# D5035-01.net
KiCad netlist of a schematic drawn in Altium Designer
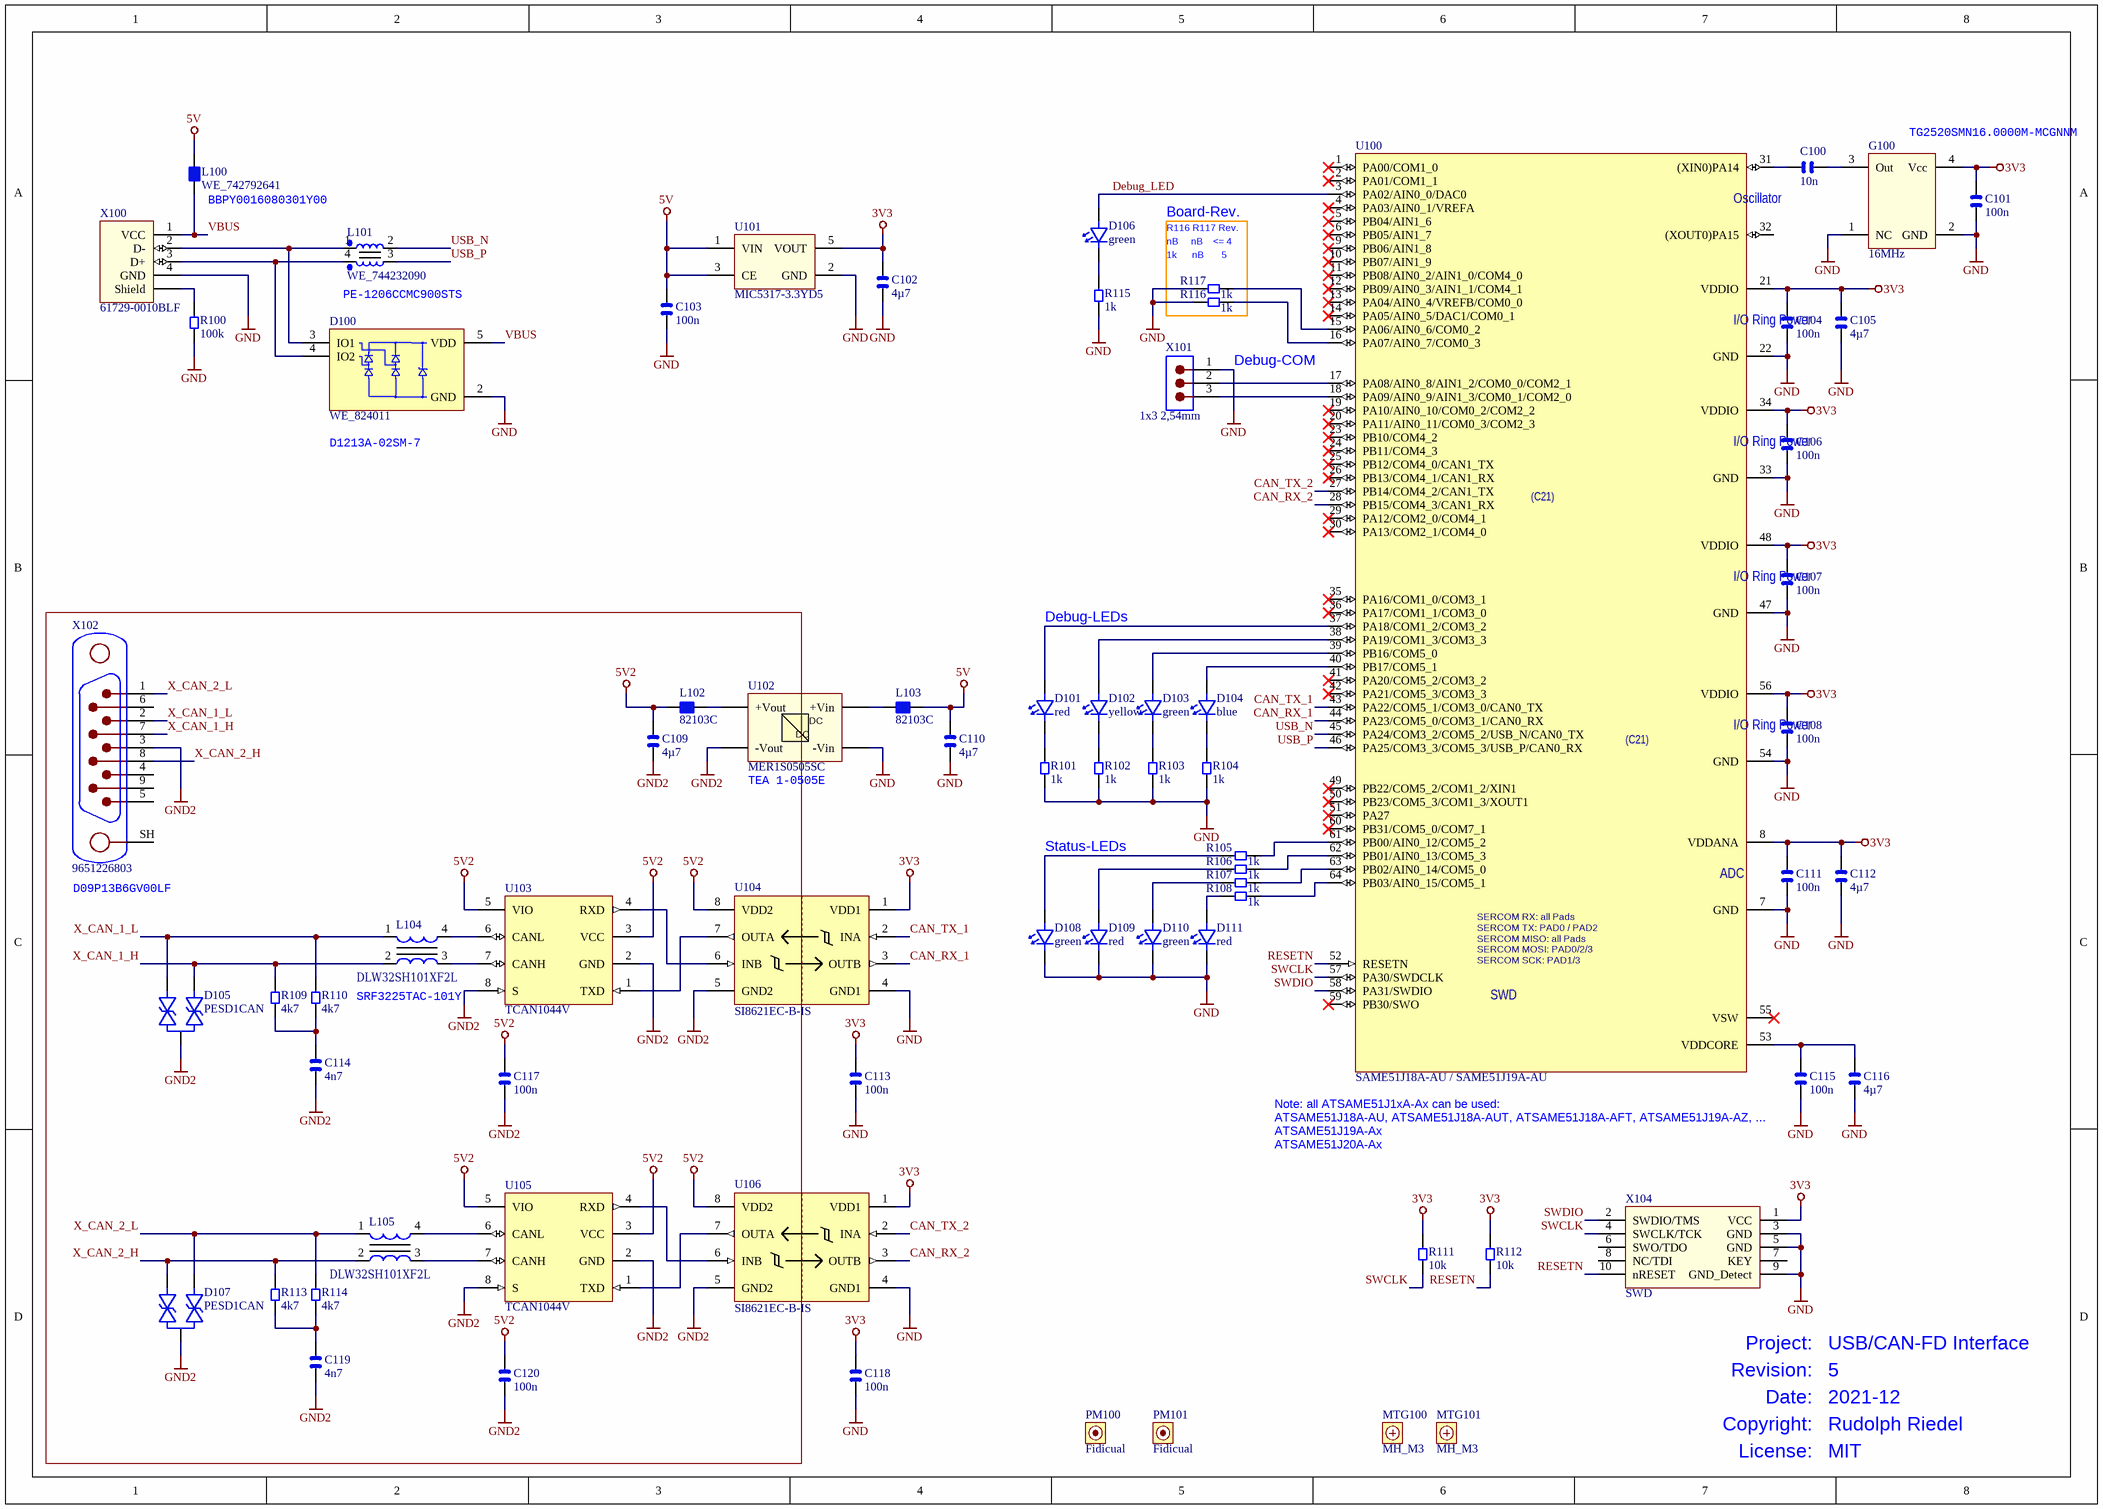
[diagram p0: D5035-01.SchDoc]

(export (version "E")
  (design (tool "Eeschema 10.0.6"))
  (components
    (comp (ref "C100")
      (value "10n")
      (footprint "CAPC1608X09L")
      (description "0603 Chip Capacitor")
      (fields (field (name "PART NUMBER") "CAPC_0603") (field (name "EDITOR") "rriedel"))
      (libsource (lib "HW-Labor_GF") (part "CAP_2_V2"))
    )
    (comp (ref "C101")
      (value "100n")
      (footprint "CAPC1608X09L")
      (description "0603 Chip Capacitor")
      (fields (field (name "PART NUMBER") "CAPC_0603") (field (name "EDITOR") "rriedel"))
      (libsource (lib "HW-Labor_GF") (part "CAP_2_V2"))
    )
    (comp (ref "C102")
      (value "4µ7")
      (footprint "CAPC2012X14L")
      (description "0805 Chip Capacitor")
      (fields (field (name "PART NUMBER") "CAPC_0805") (field (name "EDITOR") "rriedel"))
      (libsource (lib "HW-Labor_GF") (part "CAP_2_V2"))
    )
    (comp (ref "C103")
      (value "100n")
      (footprint "CAPC1608X09L")
      (description "0603 Chip Capacitor")
      (fields (field (name "PART NUMBER") "CAPC_0603") (field (name "EDITOR") "rriedel"))
      (libsource (lib "HW-Labor_GF") (part "CAP_2_V2"))
    )
    (comp (ref "C104")
      (value "100n")
      (footprint "CAPC1608X09L")
      (description "0603 Chip Capacitor")
      (fields (field (name "PART NUMBER") "CAPC_0603") (field (name "EDITOR") "rriedel"))
      (libsource (lib "HW-Labor_GF") (part "CAP_2_V2"))
    )
    (comp (ref "C105")
      (value "4µ7")
      (footprint "CAPC2012X14L")
      (description "0805 Chip Capacitor")
      (fields (field (name "PART NUMBER") "CAPC_0805") (field (name "EDITOR") "rriedel"))
      (libsource (lib "HW-Labor_GF") (part "CAP_2_V2"))
    )
    (comp (ref "C106")
      (value "100n")
      (footprint "CAPC1608X09L")
      (description "0603 Chip Capacitor")
      (fields (field (name "PART NUMBER") "CAPC_0603") (field (name "EDITOR") "rriedel"))
      (libsource (lib "HW-Labor_GF") (part "CAP_2_V2"))
    )
    (comp (ref "C107")
      (value "100n")
      (footprint "CAPC1608X09L")
      (description "0603 Chip Capacitor")
      (fields (field (name "PART NUMBER") "CAPC_0603") (field (name "EDITOR") "rriedel"))
      (libsource (lib "HW-Labor_GF") (part "CAP_2_V2"))
    )
    (comp (ref "C108")
      (value "100n")
      (footprint "CAPC1608X09L")
      (description "0603 Chip Capacitor")
      (fields (field (name "PART NUMBER") "CAPC_0603") (field (name "EDITOR") "rriedel"))
      (libsource (lib "HW-Labor_GF") (part "CAP_2_V2"))
    )
    (comp (ref "C109")
      (value "4µ7")
      (footprint "CAPC2012X14L")
      (description "0805 Chip Capacitor")
      (fields (field (name "PART NUMBER") "CAPC_0805") (field (name "EDITOR") "rriedel"))
      (libsource (lib "HW-Labor_GF") (part "CAP_2_V2"))
    )
    (comp (ref "C110")
      (value "4µ7")
      (footprint "CAPC2012X14L")
      (description "0805 Chip Capacitor")
      (fields (field (name "PART NUMBER") "CAPC_0805") (field (name "EDITOR") "rriedel"))
      (libsource (lib "HW-Labor_GF") (part "CAP_2_V2"))
    )
    (comp (ref "C111")
      (value "100n")
      (footprint "CAPC1608X09L")
      (description "0603 Chip Capacitor")
      (fields (field (name "PART NUMBER") "CAPC_0603") (field (name "EDITOR") "rriedel"))
      (libsource (lib "HW-Labor_GF") (part "CAP_2_V2"))
    )
    (comp (ref "C112")
      (value "4µ7")
      (footprint "CAPC2012X14L")
      (description "0805 Chip Capacitor")
      (fields (field (name "PART NUMBER") "CAPC_0805") (field (name "EDITOR") "rriedel"))
      (libsource (lib "HW-Labor_GF") (part "CAP_2_V2"))
    )
    (comp (ref "C113")
      (value "100n")
      (footprint "CAPC1608X09L")
      (description "0603 Chip Capacitor")
      (fields (field (name "PART NUMBER") "CAPC_0603") (field (name "EDITOR") "rriedel"))
      (libsource (lib "HW-Labor_GF") (part "CAP_2_V2"))
    )
    (comp (ref "C114")
      (value "4n7")
      (footprint "CAPC2012X14L")
      (description "0805 Chip Capacitor")
      (fields (field (name "PART NUMBER") "CAPC_0805") (field (name "EDITOR") "rriedel"))
      (libsource (lib "HW-Labor_GF") (part "CAP_2_V2"))
    )
    (comp (ref "C115")
      (value "100n")
      (footprint "CAPC1608X09L")
      (description "0603 Chip Capacitor")
      (fields (field (name "PART NUMBER") "CAPC_0603") (field (name "EDITOR") "rriedel"))
      (libsource (lib "HW-Labor_GF") (part "CAP_2_V2"))
    )
    (comp (ref "C116")
      (value "4µ7")
      (footprint "CAPC2012X14L")
      (description "0805 Chip Capacitor")
      (fields (field (name "PART NUMBER") "CAPC_0805") (field (name "EDITOR") "rriedel"))
      (libsource (lib "HW-Labor_GF") (part "CAP_2_V2"))
    )
    (comp (ref "C117")
      (value "100n")
      (footprint "CAPC1608X09L")
      (description "0603 Chip Capacitor")
      (fields (field (name "PART NUMBER") "CAPC_0603") (field (name "EDITOR") "rriedel"))
      (libsource (lib "HW-Labor_GF") (part "CAP_2_V2"))
    )
    (comp (ref "C118")
      (value "100n")
      (footprint "CAPC1608X09L")
      (description "0603 Chip Capacitor")
      (fields (field (name "PART NUMBER") "CAPC_0603") (field (name "EDITOR") "rriedel"))
      (libsource (lib "HW-Labor_GF") (part "CAP_2_V2"))
    )
    (comp (ref "C119")
      (value "4n7")
      (footprint "CAPC2012X14L")
      (description "0805 Chip Capacitor")
      (fields (field (name "PART NUMBER") "CAPC_0805") (field (name "EDITOR") "rriedel"))
      (libsource (lib "HW-Labor_GF") (part "CAP_2_V2"))
    )
    (comp (ref "C120")
      (value "100n")
      (footprint "CAPC1608X09L")
      (description "0603 Chip Capacitor")
      (fields (field (name "PART NUMBER") "CAPC_0603") (field (name "EDITOR") "rriedel"))
      (libsource (lib "HW-Labor_GF") (part "CAP_2_V2"))
    )
    (comp (ref "D100")
      (value "WE_824011")
      (footprint "SOT95P280X110-5N")
      (description "TVS Diode Array WE-TVS")
      (fields
        (field (name "MANUFACTURER") "Wuerth")
        (field (name "DISTRIBUTOR_1_PART_NUMBER") "732-4465-1-ND")
        (field (name "EDITOR") "rriedel")
      )
      (libsource (lib "HW-Labor_GF") (part "WE-824011"))
    )
    (comp (ref "D101")
      (value "red")
      (footprint "DIOC1608X06N_LED")
      (description "LED, 0603")
      (fields (field (name "PART NUMBER") "LED_0603") (field (name "EDITOR") "rriedel"))
      (libsource (lib "HW-Labor_GF") (part "LED_generic"))
    )
    (comp (ref "D102")
      (value "yellow")
      (footprint "DIOC1608X06N_LED")
      (description "LED, 0603")
      (fields (field (name "PART NUMBER") "LED_0603") (field (name "EDITOR") "rriedel"))
      (libsource (lib "HW-Labor_GF") (part "LED_generic"))
    )
    (comp (ref "D103")
      (value "green")
      (footprint "DIOC1608X06N_LED")
      (description "LED, 0603")
      (fields (field (name "PART NUMBER") "LED_0603") (field (name "EDITOR") "rriedel"))
      (libsource (lib "HW-Labor_GF") (part "LED_generic"))
    )
    (comp (ref "D104")
      (value "blue")
      (footprint "DIOC1608X06N_LED")
      (description "LED, 0603")
      (fields (field (name "PART NUMBER") "LED_0603") (field (name "EDITOR") "rriedel"))
      (libsource (lib "HW-Labor_GF") (part "LED_generic"))
    )
    (comp (ref "D105")
      (value "PESD1CAN")
      (footprint "SOT95P280X110-3N")
      (description "CAN bus ESD protection diode")
      (fields
        (field (name "MANUFACTURER") "Nexperia")
        (field (name "DISTRIBUTOR_1_PART_NUMBER") "1727-3817-1-ND")
        (field (name "EDITOR") "rriedel")
      )
      (libsource (lib "HW-Labor_GF") (part "PESD1CAN"))
    )
    (comp (ref "D106")
      (value "green")
      (footprint "DIOC1608X06N_LED")
      (description "LED, 0603")
      (fields (field (name "PART NUMBER") "LED_0603") (field (name "EDITOR") "rriedel"))
      (libsource (lib "HW-Labor_GF") (part "LED_generic"))
    )
    (comp (ref "D107")
      (value "PESD1CAN")
      (footprint "SOT95P280X110-3N")
      (description "CAN bus ESD protection diode")
      (fields
        (field (name "MANUFACTURER") "Nexperia")
        (field (name "DISTRIBUTOR_1_PART_NUMBER") "1727-3817-1-ND")
        (field (name "EDITOR") "rriedel")
      )
      (libsource (lib "HW-Labor_GF") (part "PESD1CAN"))
    )
    (comp (ref "D108")
      (value "green")
      (footprint "DIOC1608X06N_LED")
      (description "LED, 0603")
      (fields (field (name "PART NUMBER") "LED_0603") (field (name "EDITOR") "rriedel"))
      (libsource (lib "HW-Labor_GF") (part "LED_generic"))
    )
    (comp (ref "D109")
      (value "red")
      (footprint "DIOC1608X06N_LED")
      (description "LED, 0603")
      (fields (field (name "PART NUMBER") "LED_0603") (field (name "EDITOR") "rriedel"))
      (libsource (lib "HW-Labor_GF") (part "LED_generic"))
    )
    (comp (ref "D110")
      (value "green")
      (footprint "DIOC1608X06N_LED")
      (description "LED, 0603")
      (fields (field (name "PART NUMBER") "LED_0603") (field (name "EDITOR") "rriedel"))
      (libsource (lib "HW-Labor_GF") (part "LED_generic"))
    )
    (comp (ref "D111")
      (value "red")
      (footprint "DIOC1608X06N_LED")
      (description "LED, 0603")
      (fields (field (name "PART NUMBER") "LED_0603") (field (name "EDITOR") "rriedel"))
      (libsource (lib "HW-Labor_GF") (part "LED_generic"))
    )
    (comp (ref "G100")
      (value "16MHz")
      (footprint "TG2520")
      (description "16MHz Oscillator, +/- 0.5ppm")
      (fields
        (field (name "PART NUMBER") "TG2520SMN16.0000M-MCGNNM")
        (field (name "MANUFACTURER") "Epson")
        (field (name "EDITOR") "rriedel")
      )
      (libsource (lib "HW-Labor_GF") (part "TG2520"))
    )
    (comp (ref "L100")
      (value "WE_742792641")
      (footprint "INDC1608X06L")
      (description "SMT EMI suppression ferrite bead WE-CBF")
      (fields
        (field (name "MANUFACTURER") "Wuerth")
        (field (name "DISTRIBUTOR_1_PART_NUMBER") "732-1592-1-ND")
        (field (name "EDITOR") "rriedel")
      )
      (libsource (lib "HW-Labor_GF") (part "IND_2_V1"))
    )
    (comp (ref "L101")
      (value "WE_744232090")
      (footprint "WE_744232090")
      (description "SMD common mode noise suppressor WE-CNSW")
      (fields
        (field (name "MANUFACTURER") "Wuerth")
        (field (name "DISTRIBUTOR_1_PART_NUMBER") "732-1469-1-ND")
        (field (name "EDITOR") "rriedel")
      )
      (libsource (lib "HW-Labor_GF") (part "WE_744232090"))
    )
    (comp (ref "L102")
      (value "82103C")
      (footprint "Murata_8200C")
      (description "10µH, 0,5A, 400mR")
      (fields
        (field (name "MANUFACTURER") "Murata")
        (field (name "DISTRIBUTOR_1_PART_NUMBER") "811-2473-1-ND")
        (field (name "EDITOR") "rriedel")
      )
      (libsource (lib "HW-Labor_GF") (part "IND_2_V1"))
    )
    (comp (ref "L103")
      (value "82103C")
      (footprint "Murata_8200C")
      (description "10µH, 0,5A, 400mR")
      (fields
        (field (name "MANUFACTURER") "Murata")
        (field (name "DISTRIBUTOR_1_PART_NUMBER") "811-2473-1-ND")
        (field (name "EDITOR") "rriedel")
      )
      (libsource (lib "HW-Labor_GF") (part "IND_2_V1"))
    )
    (comp (ref "L104")
      (value "DLW32SH101XF2L‎")
      (footprint "ACT1210")
      (description "Common Mode Filter,  -50°C ... +150°C, AEC-Q200")
      (fields
        (field (name "PART NUMBER") "ACT1210-101-2P-TL00")
        (field (name "MANUFACTURER") "TDK")
        (field (name "EDITOR") "rriedel")
      )
      (libsource (lib "HW-Labor_GF") (part "CAN_DROSSEL"))
    )
    (comp (ref "L105")
      (value "DLW32SH101XF2L‎")
      (footprint "ACT1210")
      (description "Common Mode Filter,  -50°C ... +150°C, AEC-Q200")
      (fields
        (field (name "PART NUMBER") "ACT1210-101-2P-TL00")
        (field (name "MANUFACTURER") "TDK")
        (field (name "EDITOR") "rriedel")
      )
      (libsource (lib "HW-Labor_GF") (part "CAN_DROSSEL"))
    )
    (comp (ref "MTG100")
      (value "MH_M3")
      (footprint "HOLE_3_2MM")
      (description "Mounting-Hole for M3 screws")
      (fields (field (name "EDITOR") "rriedel"))
      (libsource (lib "HW-Labor_GF") (part "MTG_V1"))
    )
    (comp (ref "MTG101")
      (value "MH_M3")
      (footprint "HOLE_3_2MM")
      (description "Mounting-Hole for M3 screws")
      (fields (field (name "EDITOR") "rriedel"))
      (libsource (lib "HW-Labor_GF") (part "MTG_V1"))
    )
    (comp (ref "PM100")
      (value "Fidicual")
      (footprint "PM100")
      (fields (field (name "PART NUMBER") "PM100") (field (name "EDITOR") "rriedel"))
      (libsource (lib "HW-Labor_GF") (part "PM100"))
    )
    (comp (ref "PM101")
      (value "Fidicual")
      (footprint "PM100")
      (fields (field (name "PART NUMBER") "PM100") (field (name "EDITOR") "rriedel"))
      (libsource (lib "HW-Labor_GF") (part "PM100"))
    )
    (comp (ref "R100")
      (value "100k")
      (footprint "RESC2012X06L")
      (description "0805 Chip Resistor")
      (fields (field (name "PART NUMBER") "RESC_0805") (field (name "EDITOR") "rriedel"))
      (libsource (lib "HW-Labor_GF") (part "RES_2_V2"))
    )
    (comp (ref "R101")
      (value "1k")
      (footprint "RESC1608X06L")
      (description "0603 Chip Resistor")
      (fields (field (name "PART NUMBER") "RESC_0603") (field (name "EDITOR") "rriedel"))
      (libsource (lib "HW-Labor_GF") (part "RES_2_V2"))
    )
    (comp (ref "R102")
      (value "1k")
      (footprint "RESC1608X06L")
      (description "0603 Chip Resistor")
      (fields (field (name "PART NUMBER") "RESC_0603") (field (name "EDITOR") "rriedel"))
      (libsource (lib "HW-Labor_GF") (part "RES_2_V2"))
    )
    (comp (ref "R103")
      (value "1k")
      (footprint "RESC1608X06L")
      (description "0603 Chip Resistor")
      (fields (field (name "PART NUMBER") "RESC_0603") (field (name "EDITOR") "rriedel"))
      (libsource (lib "HW-Labor_GF") (part "RES_2_V2"))
    )
    (comp (ref "R104")
      (value "1k")
      (footprint "RESC1608X06L")
      (description "0603 Chip Resistor")
      (fields (field (name "PART NUMBER") "RESC_0603") (field (name "EDITOR") "rriedel"))
      (libsource (lib "HW-Labor_GF") (part "RES_2_V2"))
    )
    (comp (ref "R105")
      (value "1k")
      (footprint "RESC1608X06L")
      (description "0603 Chip Resistor")
      (fields (field (name "PART NUMBER") "RESC_0603") (field (name "EDITOR") "rriedel"))
      (libsource (lib "HW-Labor_GF") (part "RES_2_V2"))
    )
    (comp (ref "R106")
      (value "1k")
      (footprint "RESC1608X06L")
      (description "0603 Chip Resistor")
      (fields (field (name "PART NUMBER") "RESC_0603") (field (name "EDITOR") "rriedel"))
      (libsource (lib "HW-Labor_GF") (part "RES_2_V2"))
    )
    (comp (ref "R107")
      (value "1k")
      (footprint "RESC1608X06L")
      (description "0603 Chip Resistor")
      (fields (field (name "PART NUMBER") "RESC_0603") (field (name "EDITOR") "rriedel"))
      (libsource (lib "HW-Labor_GF") (part "RES_2_V2"))
    )
    (comp (ref "R108")
      (value "1k")
      (footprint "RESC1608X06L")
      (description "0603 Chip Resistor")
      (fields (field (name "PART NUMBER") "RESC_0603") (field (name "EDITOR") "rriedel"))
      (libsource (lib "HW-Labor_GF") (part "RES_2_V2"))
    )
    (comp (ref "R109")
      (value "4k7")
      (footprint "RESC2012X06L")
      (description "0805 Chip Resistor")
      (fields (field (name "PART NUMBER") "RESC_0805") (field (name "EDITOR") "rriedel"))
      (libsource (lib "HW-Labor_GF") (part "RES_2_V2"))
    )
    (comp (ref "R110")
      (value "4k7")
      (footprint "RESC2012X06L")
      (description "0805 Chip Resistor")
      (fields (field (name "PART NUMBER") "RESC_0805") (field (name "EDITOR") "rriedel"))
      (libsource (lib "HW-Labor_GF") (part "RES_2_V2"))
    )
    (comp (ref "R111")
      (value "10k")
      (footprint "RESC2012X06L")
      (description "0805 Chip Resistor")
      (fields (field (name "PART NUMBER") "RESC_0805") (field (name "EDITOR") "rriedel"))
      (libsource (lib "HW-Labor_GF") (part "RES_2_V2"))
    )
    (comp (ref "R112")
      (value "10k")
      (footprint "RESC2012X06L")
      (description "0805 Chip Resistor")
      (fields (field (name "PART NUMBER") "RESC_0805") (field (name "EDITOR") "rriedel"))
      (libsource (lib "HW-Labor_GF") (part "RES_2_V2"))
    )
    (comp (ref "R113")
      (value "4k7")
      (footprint "RESC2012X06L")
      (description "0805 Chip Resistor")
      (fields (field (name "PART NUMBER") "RESC_0805") (field (name "EDITOR") "rriedel"))
      (libsource (lib "HW-Labor_GF") (part "RES_2_V2"))
    )
    (comp (ref "R114")
      (value "4k7")
      (footprint "RESC2012X06L")
      (description "0805 Chip Resistor")
      (fields (field (name "PART NUMBER") "RESC_0805") (field (name "EDITOR") "rriedel"))
      (libsource (lib "HW-Labor_GF") (part "RES_2_V2"))
    )
    (comp (ref "R115")
      (value "1k")
      (footprint "RESC1608X06L")
      (description "0603 Chip Resistor")
      (fields (field (name "PART NUMBER") "RESC_0603") (field (name "EDITOR") "rriedel"))
      (libsource (lib "HW-Labor_GF") (part "RES_2_V2"))
    )
    (comp (ref "R116")
      (value "1k")
      (footprint "RESC1608X06L")
      (description "0603 Chip Resistor")
      (fields (field (name "PART NUMBER") "RESC_0603") (field (name "EDITOR") "rriedel"))
      (libsource (lib "HW-Labor_GF") (part "RES_2_V2"))
    )
    (comp (ref "R117")
      (value "1k")
      (footprint "RESC1608X06L")
      (description "0603 Chip Resistor")
      (fields (field (name "PART NUMBER") "RESC_0603") (field (name "EDITOR") "rriedel"))
      (libsource (lib "HW-Labor_GF") (part "RES_2_V2"))
    )
    (comp (ref "U100")
      (value "SAME51J18A-AU / SAME51J19A-AU")
      (footprint "TSQFP50P1200X1200X120-64N")
      (description "32-bit Microcontroller, 120MHz Cortex M4-F, 512k FLASH,  2x CAN-FD, -40…85°C")
      (fields
        (field (name "PART NUMBER") "SAME51J19A-AU")
        (field (name "MANUFACTURER") "Microchip")
        (field (name "EDITOR") "rriedel")
      )
      (libsource (lib "HW-Labor_GF") (part "SAME5xJxxA-AUx"))
    )
    (comp (ref "U101")
      (value "MIC5317-3.3YD5")
      (footprint "SOT95P280X110-5N")
      (description "100 mA LDO,  Vout= 3,3V, -40°C..125°C")
      (fields
        (field (name "PART NUMBER") "MIC5233-3.3")
        (field (name "MANUFACTURER") "Microchip")
        (field (name "EDITOR") "rriedel")
      )
      (libsource (lib "HW-Labor_GF") (part "LDO_SOT23-5"))
    )
    (comp (ref "U102")
      (value "MER1S0505SC")
      (footprint "MER1SxxxxC")
      (description "Isolated 1W Single Output DC-DC Converters 5V/5V 200mA")
      (fields
        (field (name "MANUFACTURER") "Murata")
        (field (name "DISTRIBUTOR_1_PART_NUMBER") "811-2124-5-ND‎")
        (field (name "EDITOR") "rriedel")
      )
      (libsource (lib "HW-Labor_GF") (part "MER1SxxxxC"))
    )
    (comp (ref "U103")
      (value "TCAN1044V")
      (footprint "SOT65P280X100-8N")
      (description "CAN-FD transceiver 8MBit, VIO Pin")
      (fields
        (field (name "MANUFACTURER") "TI")
        (field (name "DISTRIBUTOR_1_PART_NUMBER") "296-TCAN1044VDDFRCT-ND")
        (field (name "EDITOR") "rriedel")
      )
      (libsource (lib "HW-Labor_GF") (part "TJA1051T_3"))
    )
    (comp (ref "U104")
      (value "SI8621EC-B-IS")
      (footprint "SOIC127P600X175-8N")
      (description "Dual channel digital isolator, 150Mbit, 3,75kV")
      (fields
        (field (name "MANUFACTURER") "Silicon Labs")
        (field (name "DISTRIBUTOR_1_PART_NUMBER") "336-4776-1-ND")
        (field (name "EDITOR") "rriedel")
      )
      (libsource (lib "HW-Labor_GF") (part "SI8621"))
    )
    (comp (ref "U105")
      (value "TCAN1044V")
      (footprint "SOT65P280X100-8N")
      (description "CAN-FD transceiver 8MBit, VIO Pin")
      (fields
        (field (name "MANUFACTURER") "TI")
        (field (name "DISTRIBUTOR_1_PART_NUMBER") "296-TCAN1044VDDFRCT-ND")
        (field (name "EDITOR") "rriedel")
      )
      (libsource (lib "HW-Labor_GF") (part "TJA1051T_3"))
    )
    (comp (ref "U106")
      (value "SI8621EC-B-IS")
      (footprint "SOIC127P600X175-8N")
      (description "Dual channel digital isolator, 150Mbit, 3,75kV")
      (fields
        (field (name "MANUFACTURER") "Silicon Labs")
        (field (name "DISTRIBUTOR_1_PART_NUMBER") "336-4776-1-ND")
        (field (name "EDITOR") "rriedel")
      )
      (libsource (lib "HW-Labor_GF") (part "SI8621"))
    )
    (comp (ref "X100")
      (value "61729-0010BLF")
      (footprint "61729-xxxxxLF")
      (description "USB-B socket, THT")
      (fields
        (field (name "MANUFACTURER") "Amphenol")
        (field (name "DISTRIBUTOR_1_PART_NUMBER") "609-1039-ND")
        (field (name "EDITOR") "rriedel")
      )
      (libsource (lib "HW-Labor_GF") (part "USB"))
    )
    (comp (ref "X101")
      (value "1x3 2,54mm")
      (footprint "PINH_1x03_2_54mm")
      (description "Pin-Header 2,54 mm 3pins")
      (fields (field (name "PART NUMBER") "PINH_1x3_2_54") (field (name "EDITOR") "rriedel"))
      (libsource (lib "HW-Labor_GF") (part "CONM_1x3_V2"))
    )
    (comp (ref "X102")
      (value "9651226803")
      (footprint "09651226803")
      (description "D-Sub, 9 pin, male, right angle")
      (fields
        (field (name "MANUFACTURER") "Harting")
        (field (name "DISTRIBUTOR_1_PART_NUMBER") "2752007")
        (field (name "EDITOR") "rriedel")
      )
      (libsource (lib "HW-Labor_GF") (part "D_Sub_9_Male"))
    )
    (comp (ref "X104")
      (value "SWD")
      (footprint "FTSH-105-01-L-DV-K")
      (description "ARM Debug-Header 2x5 1,27 mm")
      (fields (field (name "EDITOR") "rriedel"))
      (libsource (lib "HW-Labor_GF") (part "SWD"))
    )
  )
  (nets
    (net (code "1") (name "/CAN_RX_1") (class "Default")
      (node (ref "U100") (pin "44") (pinfunction "PA23/COM5_0/COM3_1/CAN0_RX_44") (pintype "bidirectional"))
      (node (ref "U104") (pin "3") (pinfunction "OUTB_3") (pintype "output"))
    )
    (net (code "2") (name "/CAN_RX_2") (class "Default")
      (node (ref "U100") (pin "28") (pinfunction "PB15/COM4_3/CAN1_RX_28") (pintype "bidirectional"))
      (node (ref "U106") (pin "3") (pinfunction "OUTB_3") (pintype "output"))
    )
    (net (code "3") (name "/CAN_TX_1") (class "Default")
      (node (ref "U100") (pin "43") (pinfunction "PA22/COM5_1/COM3_0/CAN0_TX_43") (pintype "bidirectional"))
      (node (ref "U104") (pin "2") (pinfunction "INA_2") (pintype "input"))
    )
    (net (code "4") (name "/CAN_TX_2") (class "Default")
      (node (ref "U100") (pin "27") (pinfunction "PB14/COM4_2/CAN1_TX_27") (pintype "bidirectional"))
      (node (ref "U106") (pin "2") (pinfunction "INA_2") (pintype "input"))
    )
    (net (code "5") (name "/Debug_LED") (class "Default")
      (node (ref "D106") (pin "2") (pinfunction "2_2") (pintype "passive"))
      (node (ref "U100") (pin "3") (pinfunction "PA02/AIN0_0/DAC0_3") (pintype "bidirectional"))
    )
    (net (code "6") (name "/RESETN") (class "Default")
      (node (ref "R112") (pin "1") (pinfunction "1_1") (pintype "passive"))
      (node (ref "U100") (pin "52") (pinfunction "RESETN_52") (pintype "input"))
      (node (ref "X104") (pin "10") (pinfunction "nRESET_10") (pintype "passive"))
    )
    (net (code "7") (name "/SWCLK") (class "Default")
      (node (ref "R111") (pin "1") (pinfunction "1_1") (pintype "passive"))
      (node (ref "U100") (pin "57") (pinfunction "PA30/SWDCLK_57") (pintype "bidirectional"))
      (node (ref "X104") (pin "4") (pinfunction "SWCLK/TCK_4") (pintype "passive"))
    )
    (net (code "8") (name "/SWDIO") (class "Default")
      (node (ref "U100") (pin "58") (pinfunction "PA31/SWDIO_58") (pintype "bidirectional"))
      (node (ref "X104") (pin "2") (pinfunction "SWDIO/TMS_2") (pintype "passive"))
    )
    (net (code "9") (name "/USB_N") (class "Default")
      (node (ref "L101") (pin "2") (pinfunction "2_2") (pintype "passive"))
      (node (ref "U100") (pin "45") (pinfunction "PA24/COM3_2/COM5_2/USB_N/CAN0_TX_45") (pintype "bidirectional"))
    )
    (net (code "10") (name "/USB_P") (class "Default")
      (node (ref "L101") (pin "3") (pinfunction "3_3") (pintype "passive"))
      (node (ref "U100") (pin "46") (pinfunction "PA25/COM3_3/COM5_3/USB_P/CAN0_RX_46") (pintype "bidirectional"))
    )
    (net (code "11") (name "/VBUS") (class "Default")
      (node (ref "D100") (pin "5") (pinfunction "VDD_5") (pintype "passive"))
      (node (ref "L100") (pin "1") (pinfunction "1_1") (pintype "passive"))
      (node (ref "X100") (pin "1") (pinfunction "VCC_1") (pintype "power_in"))
    )
    (net (code "12") (name "/X_CAN_1_H") (class "Default")
      (node (ref "D105") (pin "2") (pinfunction "2_2") (pintype "passive"))
      (node (ref "L104") (pin "2") (pintype "passive"))
      (node (ref "R109") (pin "2") (pinfunction "2_2") (pintype "passive"))
      (node (ref "X102") (pin "7") (pinfunction "7_7") (pintype "passive"))
    )
    (net (code "13") (name "/X_CAN_1_L") (class "Default")
      (node (ref "D105") (pin "1") (pinfunction "1_1") (pintype "passive"))
      (node (ref "L104") (pin "1") (pintype "passive"))
      (node (ref "R110") (pin "2") (pinfunction "2_2") (pintype "passive"))
      (node (ref "X102") (pin "2") (pinfunction "2_2") (pintype "passive"))
    )
    (net (code "14") (name "/X_CAN_2_H") (class "Default")
      (node (ref "D107") (pin "1") (pinfunction "1_1") (pintype "passive"))
      (node (ref "L105") (pin "2") (pintype "passive"))
      (node (ref "R113") (pin "2") (pinfunction "2_2") (pintype "passive"))
      (node (ref "X102") (pin "8") (pinfunction "8_8") (pintype "passive"))
    )
    (net (code "15") (name "/X_CAN_2_L") (class "Default")
      (node (ref "D107") (pin "2") (pinfunction "2_2") (pintype "passive"))
      (node (ref "L105") (pin "1") (pintype "passive"))
      (node (ref "R114") (pin "2") (pinfunction "2_2") (pintype "passive"))
      (node (ref "X102") (pin "1") (pinfunction "1_1") (pintype "passive"))
    )
    (net (code "16") (name "3V3") (class "Default")
      (node (ref "C101") (pin "2") (pinfunction "2_2") (pintype "passive"))
      (node (ref "C102") (pin "2") (pinfunction "2_2") (pintype "passive"))
      (node (ref "C104") (pin "2") (pinfunction "2_2") (pintype "passive"))
      (node (ref "C105") (pin "2") (pinfunction "2_2") (pintype "passive"))
      (node (ref "C106") (pin "2") (pinfunction "2_2") (pintype "passive"))
      (node (ref "C107") (pin "2") (pinfunction "2_2") (pintype "passive"))
      (node (ref "C108") (pin "2") (pinfunction "2_2") (pintype "passive"))
      (node (ref "C111") (pin "2") (pinfunction "2_2") (pintype "passive"))
      (node (ref "C112") (pin "2") (pinfunction "2_2") (pintype "passive"))
      (node (ref "C113") (pin "2") (pinfunction "2_2") (pintype "passive"))
      (node (ref "C118") (pin "2") (pinfunction "2_2") (pintype "passive"))
      (node (ref "G100") (pin "4") (pinfunction "Vcc_4") (pintype "passive"))
      (node (ref "R111") (pin "2") (pinfunction "2_2") (pintype "passive"))
      (node (ref "R112") (pin "2") (pinfunction "2_2") (pintype "passive"))
      (node (ref "U100") (pin "21") (pinfunction "VDDIO_21") (pintype "power_in"))
      (node (ref "U100") (pin "34") (pinfunction "VDDIO_34") (pintype "power_in"))
      (node (ref "U100") (pin "48") (pinfunction "VDDIO_48") (pintype "power_in"))
      (node (ref "U100") (pin "56") (pinfunction "VDDIO_56") (pintype "power_in"))
      (node (ref "U100") (pin "8") (pinfunction "VDDANA_8") (pintype "power_in"))
      (node (ref "U101") (pin "5") (pinfunction "VOUT_5") (pintype "passive"))
      (node (ref "U104") (pin "1") (pinfunction "VDD1_1") (pintype "power_in"))
      (node (ref "U106") (pin "1") (pinfunction "VDD1_1") (pintype "power_in"))
      (node (ref "X104") (pin "1") (pinfunction "VCC_1") (pintype "power_in"))
    )
    (net (code "17") (name "5V") (class "Default")
      (node (ref "C103") (pin "2") (pinfunction "2_2") (pintype "passive"))
      (node (ref "C110") (pin "2") (pinfunction "2_2") (pintype "passive"))
      (node (ref "L100") (pin "2") (pinfunction "2_2") (pintype "passive"))
      (node (ref "L103") (pin "1") (pinfunction "1_1") (pintype "passive"))
      (node (ref "U101") (pin "1") (pinfunction "VIN_1") (pintype "passive"))
      (node (ref "U101") (pin "3") (pinfunction "CE_3") (pintype "passive"))
    )
    (net (code "18") (name "5V2") (class "Default")
      (node (ref "C109") (pin "2") (pinfunction "2_2") (pintype "passive"))
      (node (ref "C117") (pin "2") (pinfunction "2_2") (pintype "passive"))
      (node (ref "C120") (pin "2") (pinfunction "2_2") (pintype "passive"))
      (node (ref "L102") (pin "2") (pinfunction "2_2") (pintype "passive"))
      (node (ref "U103") (pin "3") (pinfunction "VCC_3") (pintype "power_in"))
      (node (ref "U103") (pin "5") (pinfunction "VIO_5") (pintype "power_in"))
      (node (ref "U104") (pin "8") (pinfunction "VDD2_8") (pintype "power_in"))
      (node (ref "U105") (pin "3") (pinfunction "VCC_3") (pintype "power_in"))
      (node (ref "U105") (pin "5") (pinfunction "VIO_5") (pintype "power_in"))
      (node (ref "U106") (pin "8") (pinfunction "VDD2_8") (pintype "power_in"))
    )
    (net (code "19") (name "GND") (class "Default")
      (node (ref "C101") (pin "1") (pinfunction "1_1") (pintype "passive"))
      (node (ref "C102") (pin "1") (pinfunction "1_1") (pintype "passive"))
      (node (ref "C103") (pin "1") (pinfunction "1_1") (pintype "passive"))
      (node (ref "C104") (pin "1") (pinfunction "1_1") (pintype "passive"))
      (node (ref "C105") (pin "1") (pinfunction "1_1") (pintype "passive"))
      (node (ref "C106") (pin "1") (pinfunction "1_1") (pintype "passive"))
      (node (ref "C107") (pin "1") (pinfunction "1_1") (pintype "passive"))
      (node (ref "C108") (pin "1") (pinfunction "1_1") (pintype "passive"))
      (node (ref "C110") (pin "1") (pinfunction "1_1") (pintype "passive"))
      (node (ref "C111") (pin "1") (pinfunction "1_1") (pintype "passive"))
      (node (ref "C112") (pin "1") (pinfunction "1_1") (pintype "passive"))
      (node (ref "C113") (pin "1") (pinfunction "1_1") (pintype "passive"))
      (node (ref "C115") (pin "1") (pinfunction "1_1") (pintype "passive"))
      (node (ref "C116") (pin "1") (pinfunction "1_1") (pintype "passive"))
      (node (ref "C118") (pin "1") (pinfunction "1_1") (pintype "passive"))
      (node (ref "D100") (pin "2") (pinfunction "GND_2") (pintype "passive"))
      (node (ref "D108") (pin "1") (pinfunction "1_1") (pintype "passive"))
      (node (ref "D109") (pin "1") (pinfunction "1_1") (pintype "passive"))
      (node (ref "D110") (pin "1") (pinfunction "1_1") (pintype "passive"))
      (node (ref "D111") (pin "1") (pinfunction "1_1") (pintype "passive"))
      (node (ref "G100") (pin "1") (pinfunction "NC_1") (pintype "passive"))
      (node (ref "G100") (pin "2") (pinfunction "GND_2") (pintype "power_in"))
      (node (ref "R100") (pin "1") (pinfunction "1_1") (pintype "passive"))
      (node (ref "R101") (pin "1") (pinfunction "1_1") (pintype "passive"))
      (node (ref "R102") (pin "1") (pinfunction "1_1") (pintype "passive"))
      (node (ref "R103") (pin "1") (pinfunction "1_1") (pintype "passive"))
      (node (ref "R104") (pin "1") (pinfunction "1_1") (pintype "passive"))
      (node (ref "R115") (pin "1") (pinfunction "1_1") (pintype "passive"))
      (node (ref "R116") (pin "2") (pinfunction "2_2") (pintype "passive"))
      (node (ref "R117") (pin "2") (pinfunction "2_2") (pintype "passive"))
      (node (ref "U100") (pin "22") (pinfunction "GND_22") (pintype "power_in"))
      (node (ref "U100") (pin "33") (pinfunction "GND_33") (pintype "power_in"))
      (node (ref "U100") (pin "47") (pinfunction "GND_47") (pintype "power_in"))
      (node (ref "U100") (pin "54") (pinfunction "GND_54") (pintype "power_in"))
      (node (ref "U100") (pin "7") (pinfunction "GND_7") (pintype "power_in"))
      (node (ref "U101") (pin "2") (pinfunction "GND_2") (pintype "passive"))
      (node (ref "U102") (pin "2") (pinfunction "-Vin_2") (pintype "power_in"))
      (node (ref "U104") (pin "4") (pinfunction "GND1_4") (pintype "power_in"))
      (node (ref "U106") (pin "4") (pinfunction "GND1_4") (pintype "power_in"))
      (node (ref "X100") (pin "4") (pinfunction "GND_4") (pintype "power_in"))
      (node (ref "X101") (pin "1") (pinfunction "1_1") (pintype "passive"))
      (node (ref "X104") (pin "3") (pinfunction "GND_3") (pintype "power_in"))
      (node (ref "X104") (pin "5") (pinfunction "GND_5") (pintype "power_in"))
      (node (ref "X104") (pin "9") (pinfunction "GND_Detect_9") (pintype "power_in"))
    )
    (net (code "20") (name "GND2") (class "Default")
      (node (ref "C109") (pin "1") (pinfunction "1_1") (pintype "passive"))
      (node (ref "C114") (pin "1") (pinfunction "1_1") (pintype "passive"))
      (node (ref "C117") (pin "1") (pinfunction "1_1") (pintype "passive"))
      (node (ref "C119") (pin "1") (pinfunction "1_1") (pintype "passive"))
      (node (ref "C120") (pin "1") (pinfunction "1_1") (pintype "passive"))
      (node (ref "D105") (pin "3") (pinfunction "3_3") (pintype "passive"))
      (node (ref "D107") (pin "3") (pinfunction "3_3") (pintype "passive"))
      (node (ref "U102") (pin "4") (pinfunction "-Vout_4") (pintype "power_in"))
      (node (ref "U103") (pin "2") (pinfunction "GND_2") (pintype "power_in"))
      (node (ref "U103") (pin "8") (pinfunction "S_8") (pintype "input"))
      (node (ref "U104") (pin "5") (pinfunction "GND2_5") (pintype "power_in"))
      (node (ref "U105") (pin "2") (pinfunction "GND_2") (pintype "power_in"))
      (node (ref "U105") (pin "8") (pinfunction "S_8") (pintype "input"))
      (node (ref "U106") (pin "5") (pinfunction "GND2_5") (pintype "power_in"))
      (node (ref "X102") (pin "3") (pinfunction "3_3") (pintype "passive"))
    )
    (net (code "21") (name "Net-(C114-Pad2)") (class "Default")
      (node (ref "C114") (pin "2") (pinfunction "2_2") (pintype "passive"))
      (node (ref "R109") (pin "1") (pinfunction "1_1") (pintype "passive"))
      (node (ref "R110") (pin "1") (pinfunction "1_1") (pintype "passive"))
    )
    (net (code "22") (name "Net-(C119-Pad2)") (class "Default")
      (node (ref "C119") (pin "2") (pinfunction "2_2") (pintype "passive"))
      (node (ref "R113") (pin "1") (pinfunction "1_1") (pintype "passive"))
      (node (ref "R114") (pin "1") (pinfunction "1_1") (pintype "passive"))
    )
    (net (code "23") (name "Net-(D100-IO1)") (class "Default")
      (node (ref "D100") (pin "3") (pinfunction "IO1_3") (pintype "passive"))
      (node (ref "L101") (pin "1") (pinfunction "1_1") (pintype "passive"))
      (node (ref "X100") (pin "2") (pinfunction "D-_2") (pintype "bidirectional"))
    )
    (net (code "24") (name "Net-(D100-IO2)") (class "Default")
      (node (ref "D100") (pin "4") (pinfunction "IO2_4") (pintype "passive"))
      (node (ref "L101") (pin "4") (pinfunction "4_4") (pintype "passive"))
      (node (ref "X100") (pin "3") (pinfunction "D+_3") (pintype "bidirectional"))
    )
    (net (code "25") (name "Net-(D101-Pad1)") (class "Default")
      (node (ref "D101") (pin "1") (pinfunction "1_1") (pintype "passive"))
      (node (ref "R101") (pin "2") (pinfunction "2_2") (pintype "passive"))
    )
    (net (code "26") (name "Net-(D102-Pad1)") (class "Default")
      (node (ref "D102") (pin "1") (pinfunction "1_1") (pintype "passive"))
      (node (ref "R102") (pin "2") (pinfunction "2_2") (pintype "passive"))
    )
    (net (code "27") (name "Net-(D103-Pad1)") (class "Default")
      (node (ref "D103") (pin "1") (pinfunction "1_1") (pintype "passive"))
      (node (ref "R103") (pin "2") (pinfunction "2_2") (pintype "passive"))
    )
    (net (code "28") (name "Net-(D104-Pad1)") (class "Default")
      (node (ref "D104") (pin "1") (pinfunction "1_1") (pintype "passive"))
      (node (ref "R104") (pin "2") (pinfunction "2_2") (pintype "passive"))
    )
    (net (code "29") (name "Net-(D106-Pad1)") (class "Default")
      (node (ref "D106") (pin "1") (pinfunction "1_1") (pintype "passive"))
      (node (ref "R115") (pin "2") (pinfunction "2_2") (pintype "passive"))
    )
    (net (code "30") (name "Net-(D108-Pad2)") (class "Default")
      (node (ref "D108") (pin "2") (pinfunction "2_2") (pintype "passive"))
      (node (ref "R105") (pin "1") (pinfunction "1_1") (pintype "passive"))
    )
    (net (code "31") (name "Net-(D109-Pad2)") (class "Default")
      (node (ref "D109") (pin "2") (pinfunction "2_2") (pintype "passive"))
      (node (ref "R106") (pin "1") (pinfunction "1_1") (pintype "passive"))
    )
    (net (code "32") (name "Net-(D110-Pad2)") (class "Default")
      (node (ref "D110") (pin "2") (pinfunction "2_2") (pintype "passive"))
      (node (ref "R107") (pin "1") (pinfunction "1_1") (pintype "passive"))
    )
    (net (code "33") (name "Net-(D111-Pad2)") (class "Default")
      (node (ref "D111") (pin "2") (pinfunction "2_2") (pintype "passive"))
      (node (ref "R108") (pin "1") (pinfunction "1_1") (pintype "passive"))
    )
    (net (code "34") (name "Net-(G100-Out)") (class "Default")
      (node (ref "C100") (pin "2") (pinfunction "2_2") (pintype "passive"))
      (node (ref "G100") (pin "3") (pinfunction "Out_3") (pintype "passive"))
    )
    (net (code "35") (name "Net-(U100-(XIN0)PA14)") (class "Default")
      (node (ref "C100") (pin "1") (pinfunction "1_1") (pintype "passive"))
      (node (ref "U100") (pin "31") (pinfunction "(XIN0)PA14_31") (pintype "bidirectional"))
    )
    (net (code "36") (name "Net-(U100-PA06{slash}AIN0_6{slash}COM0_2)") (class "Default")
      (node (ref "R117") (pin "1") (pinfunction "1_1") (pintype "passive"))
      (node (ref "U100") (pin "15") (pinfunction "PA06/AIN0_6/COM0_2_15") (pintype "bidirectional"))
    )
    (net (code "37") (name "Net-(U100-PA07{slash}AIN0_7{slash}COM0_3)") (class "Default")
      (node (ref "R116") (pin "1") (pinfunction "1_1") (pintype "passive"))
      (node (ref "U100") (pin "16") (pinfunction "PA07/AIN0_7/COM0_3_16") (pintype "bidirectional"))
    )
    (net (code "38") (name "Net-(U100-PA08{slash}AIN0_8{slash}AIN1_2{slash}COM0_0{slash}COM2_1)") (class "Default")
      (node (ref "U100") (pin "17") (pinfunction "PA08/AIN0_8/AIN1_2/COM0_0/COM2_1_17") (pintype "bidirectional"))
      (node (ref "X101") (pin "2") (pinfunction "2_2") (pintype "passive"))
    )
    (net (code "39") (name "Net-(U100-PA09{slash}AIN0_9{slash}AIN1_3{slash}COM0_1{slash}COM2_0)") (class "Default")
      (node (ref "U100") (pin "18") (pinfunction "PA09/AIN0_9/AIN1_3/COM0_1/COM2_0_18") (pintype "bidirectional"))
      (node (ref "X101") (pin "3") (pinfunction "3_3") (pintype "passive"))
    )
    (net (code "40") (name "Net-(U100-PA18{slash}COM1_2{slash}COM3_2)") (class "Default")
      (node (ref "D101") (pin "2") (pinfunction "2_2") (pintype "passive"))
      (node (ref "U100") (pin "37") (pinfunction "PA18/COM1_2/COM3_2_37") (pintype "bidirectional"))
    )
    (net (code "41") (name "Net-(U100-PA19{slash}COM1_3{slash}COM3_3)") (class "Default")
      (node (ref "D102") (pin "2") (pinfunction "2_2") (pintype "passive"))
      (node (ref "U100") (pin "38") (pinfunction "PA19/COM1_3/COM3_3_38") (pintype "bidirectional"))
    )
    (net (code "42") (name "Net-(U100-PB00{slash}AIN0_12{slash}COM5_2)") (class "Default")
      (node (ref "R105") (pin "2") (pinfunction "2_2") (pintype "passive"))
      (node (ref "U100") (pin "61") (pinfunction "PB00/AIN0_12/COM5_2_61") (pintype "bidirectional"))
    )
    (net (code "43") (name "Net-(U100-PB01{slash}AIN0_13{slash}COM5_3)") (class "Default")
      (node (ref "R106") (pin "2") (pinfunction "2_2") (pintype "passive"))
      (node (ref "U100") (pin "62") (pinfunction "PB01/AIN0_13/COM5_3_62") (pintype "bidirectional"))
    )
    (net (code "44") (name "Net-(U100-PB02{slash}AIN0_14{slash}COM5_0)") (class "Default")
      (node (ref "R107") (pin "2") (pinfunction "2_2") (pintype "passive"))
      (node (ref "U100") (pin "63") (pinfunction "PB02/AIN0_14/COM5_0_63") (pintype "bidirectional"))
    )
    (net (code "45") (name "Net-(U100-PB03{slash}AIN0_15{slash}COM5_1)") (class "Default")
      (node (ref "R108") (pin "2") (pinfunction "2_2") (pintype "passive"))
      (node (ref "U100") (pin "64") (pinfunction "PB03/AIN0_15/COM5_1_64") (pintype "bidirectional"))
    )
    (net (code "46") (name "Net-(U100-PB16{slash}COM5_0)") (class "Default")
      (node (ref "D103") (pin "2") (pinfunction "2_2") (pintype "passive"))
      (node (ref "U100") (pin "39") (pinfunction "PB16/COM5_0_39") (pintype "bidirectional"))
    )
    (net (code "47") (name "Net-(U100-PB17{slash}COM5_1)") (class "Default")
      (node (ref "D104") (pin "2") (pinfunction "2_2") (pintype "passive"))
      (node (ref "U100") (pin "40") (pinfunction "PB17/COM5_1_40") (pintype "bidirectional"))
    )
    (net (code "48") (name "Net-(U100-VDDCORE)") (class "Default")
      (node (ref "C115") (pin "2") (pinfunction "2_2") (pintype "passive"))
      (node (ref "C116") (pin "2") (pinfunction "2_2") (pintype "passive"))
      (node (ref "U100") (pin "53") (pinfunction "VDDCORE_53") (pintype "passive"))
    )
    (net (code "49") (name "Net-(U102-+Vin)") (class "Default")
      (node (ref "L103") (pin "2") (pinfunction "2_2") (pintype "passive"))
      (node (ref "U102") (pin "1") (pinfunction "+Vin_1") (pintype "power_in"))
    )
    (net (code "50") (name "Net-(U102-+Vout)") (class "Default")
      (node (ref "L102") (pin "1") (pinfunction "1_1") (pintype "passive"))
      (node (ref "U102") (pin "6") (pinfunction "+Vout_6") (pintype "power_in"))
    )
    (net (code "51") (name "Net-(U103-CANH)") (class "Default")
      (node (ref "L104") (pin "3") (pintype "passive"))
      (node (ref "U103") (pin "7") (pinfunction "CANH_7") (pintype "bidirectional"))
    )
    (net (code "52") (name "Net-(U103-CANL)") (class "Default")
      (node (ref "L104") (pin "4") (pintype "passive"))
      (node (ref "U103") (pin "6") (pinfunction "CANL_6") (pintype "bidirectional"))
    )
    (net (code "53") (name "Net-(U103-RXD)") (class "Default")
      (node (ref "U103") (pin "4") (pinfunction "RXD_4") (pintype "output"))
      (node (ref "U104") (pin "6") (pinfunction "INB_6") (pintype "input"))
    )
    (net (code "54") (name "Net-(U103-TXD)") (class "Default")
      (node (ref "U103") (pin "1") (pinfunction "TXD_1") (pintype "input"))
      (node (ref "U104") (pin "7") (pinfunction "OUTA_7") (pintype "output"))
    )
    (net (code "55") (name "Net-(U105-CANH)") (class "Default")
      (node (ref "L105") (pin "3") (pintype "passive"))
      (node (ref "U105") (pin "7") (pinfunction "CANH_7") (pintype "bidirectional"))
    )
    (net (code "56") (name "Net-(U105-CANL)") (class "Default")
      (node (ref "L105") (pin "4") (pintype "passive"))
      (node (ref "U105") (pin "6") (pinfunction "CANL_6") (pintype "bidirectional"))
    )
    (net (code "57") (name "Net-(U105-RXD)") (class "Default")
      (node (ref "U105") (pin "4") (pinfunction "RXD_4") (pintype "output"))
      (node (ref "U106") (pin "6") (pinfunction "INB_6") (pintype "input"))
    )
    (net (code "58") (name "Net-(U105-TXD)") (class "Default")
      (node (ref "U105") (pin "1") (pinfunction "TXD_1") (pintype "input"))
      (node (ref "U106") (pin "7") (pinfunction "OUTA_7") (pintype "output"))
    )
    (net (code "59") (name "Net-(X100-Shield)") (class "Default")
      (node (ref "R100") (pin "2") (pinfunction "2_2") (pintype "passive"))
      (node (ref "X100") (pin "Shell") (pinfunction "Shield_Shell") (pintype "passive"))
    )
    (net (code "60") (name "unconnected-(U100-(XOUT0)PA15-Pad32)") (class "Default")
      (node (ref "U100") (pin "32") (pinfunction "(XOUT0)PA15_32") (pintype "bidirectional"))
    )
    (net (code "61") (name "unconnected-(U100-PA00{slash}COM1_0-Pad1)") (class "Default")
      (node (ref "U100") (pin "1") (pinfunction "PA00/COM1_0_1") (pintype "bidirectional+no_connect"))
    )
    (net (code "62") (name "unconnected-(U100-PA01{slash}COM1_1-Pad2)") (class "Default")
      (node (ref "U100") (pin "2") (pinfunction "PA01/COM1_1_2") (pintype "bidirectional+no_connect"))
    )
    (net (code "63") (name "unconnected-(U100-PA03{slash}AIN0_1{slash}VREFA-Pad4)") (class "Default")
      (node (ref "U100") (pin "4") (pinfunction "PA03/AIN0_1/VREFA_4") (pintype "bidirectional+no_connect"))
    )
    (net (code "64") (name "unconnected-(U100-PA04{slash}AIN0_4{slash}VREFB{slash}COM0_0-Pad13)") (class "Default")
      (node (ref "U100") (pin "13") (pinfunction "PA04/AIN0_4/VREFB/COM0_0_13") (pintype "bidirectional+no_connect"))
    )
    (net (code "65") (name "unconnected-(U100-PA05{slash}AIN0_5{slash}DAC1{slash}COM0_1-Pad14)") (class "Default")
      (node (ref "U100") (pin "14") (pinfunction "PA05/AIN0_5/DAC1/COM0_1_14") (pintype "bidirectional+no_connect"))
    )
    (net (code "66") (name "unconnected-(U100-PA10{slash}AIN0_10{slash}COM0_2{slash}COM2_2-Pad19)") (class "Default")
      (node (ref "U100") (pin "19") (pinfunction "PA10/AIN0_10/COM0_2/COM2_2_19") (pintype "bidirectional+no_connect"))
    )
    (net (code "67") (name "unconnected-(U100-PA11{slash}AIN0_11{slash}COM0_3{slash}COM2_3-Pad20)") (class "Default")
      (node (ref "U100") (pin "20") (pinfunction "PA11/AIN0_11/COM0_3/COM2_3_20") (pintype "bidirectional+no_connect"))
    )
    (net (code "68") (name "unconnected-(U100-PA12{slash}COM2_0{slash}COM4_1-Pad29)") (class "Default")
      (node (ref "U100") (pin "29") (pinfunction "PA12/COM2_0/COM4_1_29") (pintype "bidirectional+no_connect"))
    )
    (net (code "69") (name "unconnected-(U100-PA13{slash}COM2_1{slash}COM4_0-Pad30)") (class "Default")
      (node (ref "U100") (pin "30") (pinfunction "PA13/COM2_1/COM4_0_30") (pintype "bidirectional+no_connect"))
    )
    (net (code "70") (name "unconnected-(U100-PA16{slash}COM1_0{slash}COM3_1-Pad35)") (class "Default")
      (node (ref "U100") (pin "35") (pinfunction "PA16/COM1_0/COM3_1_35") (pintype "bidirectional+no_connect"))
    )
    (net (code "71") (name "unconnected-(U100-PA17{slash}COM1_1{slash}COM3_0-Pad36)") (class "Default")
      (node (ref "U100") (pin "36") (pinfunction "PA17/COM1_1/COM3_0_36") (pintype "bidirectional+no_connect"))
    )
    (net (code "72") (name "unconnected-(U100-PA20{slash}COM5_2{slash}COM3_2-Pad41)") (class "Default")
      (node (ref "U100") (pin "41") (pinfunction "PA20/COM5_2/COM3_2_41") (pintype "bidirectional+no_connect"))
    )
    (net (code "73") (name "unconnected-(U100-PA21{slash}COM5_3{slash}COM3_3-Pad42)") (class "Default")
      (node (ref "U100") (pin "42") (pinfunction "PA21/COM5_3/COM3_3_42") (pintype "bidirectional+no_connect"))
    )
    (net (code "74") (name "unconnected-(U100-PA27-Pad51)") (class "Default")
      (node (ref "U100") (pin "51") (pinfunction "PA27_51") (pintype "bidirectional+no_connect"))
    )
    (net (code "75") (name "unconnected-(U100-PB04{slash}AIN1_6-Pad5)") (class "Default")
      (node (ref "U100") (pin "5") (pinfunction "PB04/AIN1_6_5") (pintype "bidirectional+no_connect"))
    )
    (net (code "76") (name "unconnected-(U100-PB05{slash}AIN1_7-Pad6)") (class "Default")
      (node (ref "U100") (pin "6") (pinfunction "PB05/AIN1_7_6") (pintype "bidirectional+no_connect"))
    )
    (net (code "77") (name "unconnected-(U100-PB06{slash}AIN1_8-Pad9)") (class "Default")
      (node (ref "U100") (pin "9") (pinfunction "PB06/AIN1_8_9") (pintype "bidirectional+no_connect"))
    )
    (net (code "78") (name "unconnected-(U100-PB07{slash}AIN1_9-Pad10)") (class "Default")
      (node (ref "U100") (pin "10") (pinfunction "PB07/AIN1_9_10") (pintype "bidirectional+no_connect"))
    )
    (net (code "79") (name "unconnected-(U100-PB08{slash}AIN0_2{slash}AIN1_0{slash}COM4_0-Pad11)") (class "Default")
      (node (ref "U100") (pin "11") (pinfunction "PB08/AIN0_2/AIN1_0/COM4_0_11") (pintype "bidirectional+no_connect"))
    )
    (net (code "80") (name "unconnected-(U100-PB09{slash}AIN0_3{slash}AIN1_1{slash}COM4_1-Pad12)") (class "Default")
      (node (ref "U100") (pin "12") (pinfunction "PB09/AIN0_3/AIN1_1/COM4_1_12") (pintype "bidirectional+no_connect"))
    )
    (net (code "81") (name "unconnected-(U100-PB10{slash}COM4_2-Pad23)") (class "Default")
      (node (ref "U100") (pin "23") (pinfunction "PB10/COM4_2_23") (pintype "bidirectional+no_connect"))
    )
    (net (code "82") (name "unconnected-(U100-PB11{slash}COM4_3-Pad24)") (class "Default")
      (node (ref "U100") (pin "24") (pinfunction "PB11/COM4_3_24") (pintype "bidirectional+no_connect"))
    )
    (net (code "83") (name "unconnected-(U100-PB12{slash}COM4_0{slash}CAN1_TX-Pad25)") (class "Default")
      (node (ref "U100") (pin "25") (pinfunction "PB12/COM4_0/CAN1_TX_25") (pintype "bidirectional+no_connect"))
    )
    (net (code "84") (name "unconnected-(U100-PB13{slash}COM4_1{slash}CAN1_RX-Pad26)") (class "Default")
      (node (ref "U100") (pin "26") (pinfunction "PB13/COM4_1/CAN1_RX_26") (pintype "bidirectional+no_connect"))
    )
    (net (code "85") (name "unconnected-(U100-PB22{slash}COM5_2{slash}COM1_2{slash}XIN1-Pad49)") (class "Default")
      (node (ref "U100") (pin "49") (pinfunction "PB22/COM5_2/COM1_2/XIN1_49") (pintype "bidirectional+no_connect"))
    )
    (net (code "86") (name "unconnected-(U100-PB23{slash}COM5_3{slash}COM1_3{slash}XOUT1-Pad50)") (class "Default")
      (node (ref "U100") (pin "50") (pinfunction "PB23/COM5_3/COM1_3/XOUT1_50") (pintype "bidirectional+no_connect"))
    )
    (net (code "87") (name "unconnected-(U100-PB30{slash}SWO-Pad59)") (class "Default")
      (node (ref "U100") (pin "59") (pinfunction "PB30/SWO_59") (pintype "bidirectional+no_connect"))
    )
    (net (code "88") (name "unconnected-(U100-PB31{slash}COM5_0{slash}COM7_1-Pad60)") (class "Default")
      (node (ref "U100") (pin "60") (pinfunction "PB31/COM5_0/COM7_1_60") (pintype "bidirectional+no_connect"))
    )
    (net (code "89") (name "unconnected-(U100-VSW-Pad55)") (class "Default")
      (node (ref "U100") (pin "55") (pinfunction "VSW_55") (pintype "passive+no_connect"))
    )
    (net (code "90") (name "unconnected-(X102-Pad4)") (class "Default")
      (node (ref "X102") (pin "4") (pinfunction "4_4") (pintype "passive"))
    )
    (net (code "91") (name "unconnected-(X102-Pad5)") (class "Default")
      (node (ref "X102") (pin "5") (pinfunction "5_5") (pintype "passive"))
    )
    (net (code "92") (name "unconnected-(X102-Pad6)") (class "Default")
      (node (ref "X102") (pin "6") (pinfunction "6_6") (pintype "passive"))
    )
    (net (code "93") (name "unconnected-(X102-Pad9)") (class "Default")
      (node (ref "X102") (pin "9") (pinfunction "9_9") (pintype "passive"))
    )
    (net (code "94") (name "unconnected-(X102-PadSH)") (class "Default")
      (node (ref "X102") (pin "SH") (pinfunction "SH_SH") (pintype "passive"))
    )
    (net (code "95") (name "unconnected-(X104-KEY-Pad7)") (class "Default")
      (node (ref "X104") (pin "7") (pinfunction "KEY_7") (pintype "passive"))
    )
    (net (code "96") (name "unconnected-(X104-NC{slash}TDI-Pad8)") (class "Default")
      (node (ref "X104") (pin "8") (pinfunction "NC/TDI_8") (pintype "passive"))
    )
    (net (code "97") (name "unconnected-(X104-SWO{slash}TDO-Pad6)") (class "Default")
      (node (ref "X104") (pin "6") (pinfunction "SWO/TDO_6") (pintype "passive"))
    )
  )
)
